# Sintetizador1.net
KiCad netlist of a schematic drawn in Altium Designer
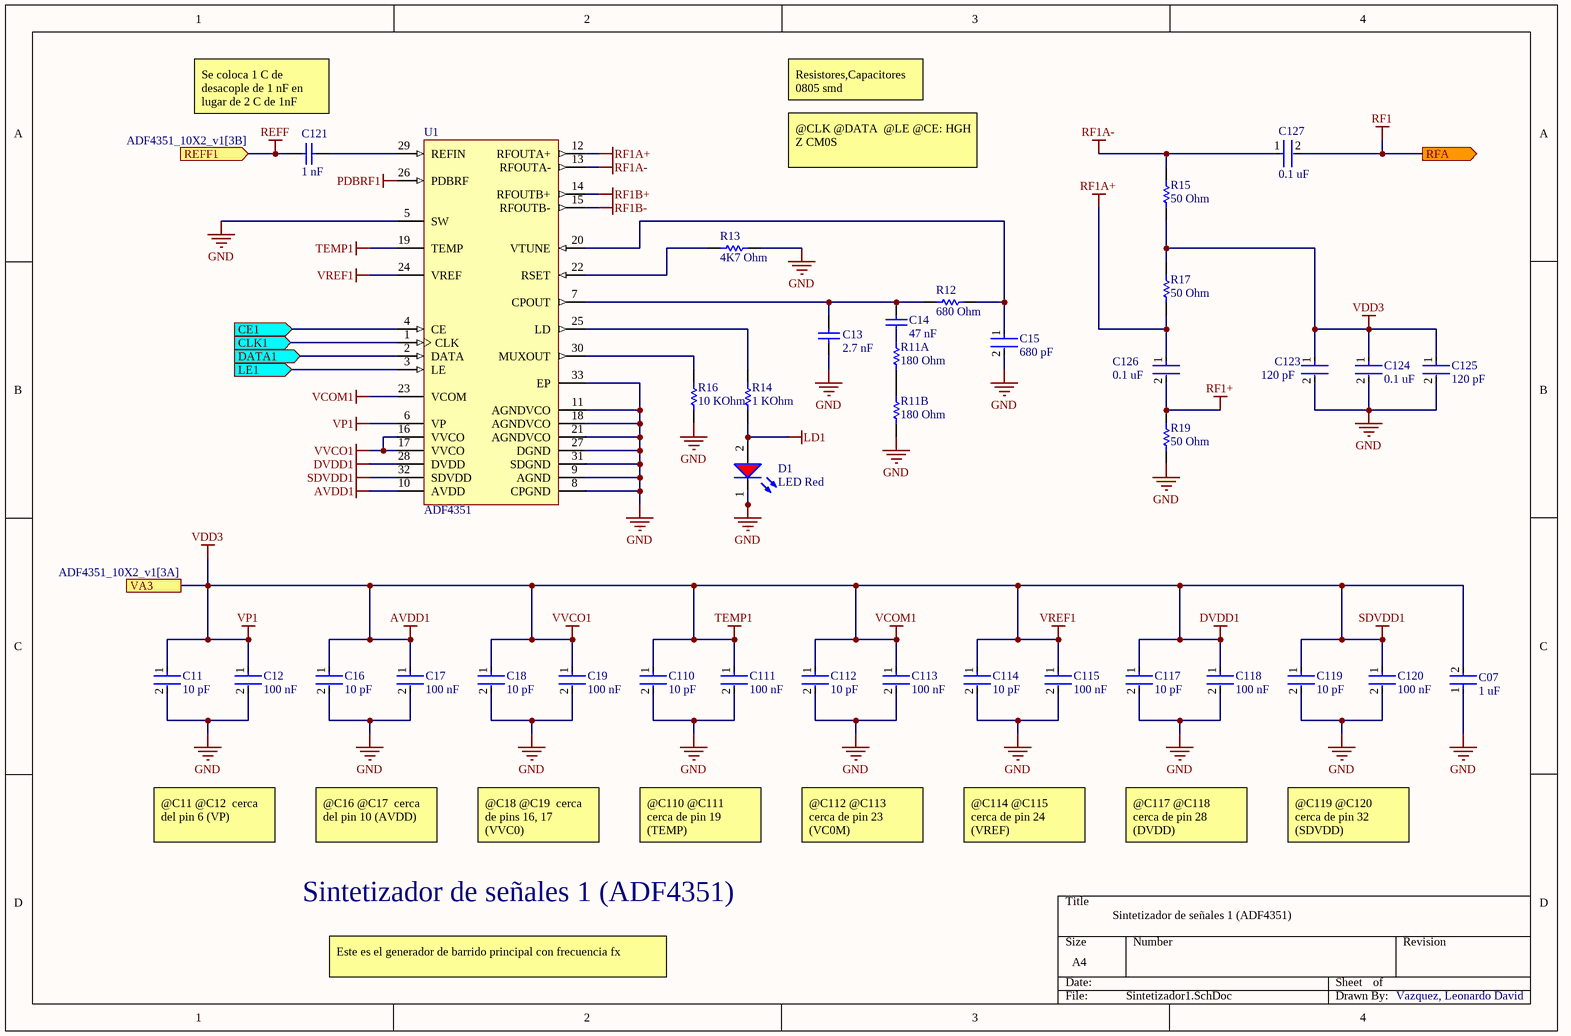
[diagram p0: Sintetizador1.SchDoc]

(export (version "E")
  (design (tool "Eeschema 10.0.6"))
  (components
    (comp (ref "C07")
      (value "1 uF")
      (footprint "FP-CC0805-0_85-MFG")
      (description "CAP CER 0.1UF 50V X7R 0805")
      (fields (field (name "TOLERANCE") "0.1") (field (name "MANUFACTURER PART NUMBER") "CC0805KRX7R9BB104"))
      (libsource (lib "Altium Content Vault") (part "11868f565c42a9108669ba33697ecf6"))
    )
    (comp (ref "C11")
      (value "10 pF")
      (footprint "FP-CL21-IPC_C")
      (description "CL21 Series 0805 10pF 100V ±0.25pF Tolerance C0G Multilayer Ceramic Chip Capacitor")
      (fields (field (name "VOLTAGE") "100V"))
      (libsource (lib "Altium Content Vault") (part "b4654b650e69147ec39a6b967a45e02"))
    )
    (comp (ref "C12")
      (value "100 nF")
      (footprint "FP-CL21-IPC_C")
      (description "CAP CER 0.1UF 50V X7R 0805")
      (fields (field (name "TOLERANCE") "0.1") (field (name "MANUFACTURER PART NUMBER") "CC0805KRX7R9BB104"))
      (libsource (lib "Altium Content Vault") (part "11868f565c42a9108669ba33697ecf6"))
    )
    (comp (ref "C13")
      (value "2.7 nF")
      (footprint "CAPC2013X130X50NL20T20")
      (fields (field (name "PART NUMBER") "CDR31BX272BKMSAJ") (field (name "MANUFACTURER") "Vitramon"))
      (libsource (lib "Altium Content Vault") (part "CAP"))
    )
    (comp (ref "C14")
      (value "47 nF")
      (footprint "CAPC2013X100X50ML20T25")
      (fields (field (name "MANUFACTURER") "Kemet") (field (name "PART NUMBER") "C0805F473K5RACTU"))
      (libsource (lib "Altium Content Vault") (part "CAP"))
    )
    (comp (ref "C15")
      (value "680 pF")
      (footprint "FP-C0805C-DN-MFG")
      (description "CAP CER 680PF 100V 5% NP0 0805")
      (fields
        (field (name "OCTOPART") "https://octopart.com/c0805c681j1gactu-kemet-8375796")
        (field (name "MANUFACTURER") "KEMET")
      )
      (libsource (lib "Altium Content Vault") (part "b4654b650e69147ec39a6b967a45e02"))
    )
    (comp (ref "C16")
      (value "10 pF")
      (footprint "FP-CL21-IPC_C")
      (description "CL21 Series 0805 10pF 100V ±0.25pF Tolerance C0G Multilayer Ceramic Chip Capacitor")
      (fields (field (name "VOLTAGE") "100V"))
      (libsource (lib "Altium Content Vault") (part "b4654b650e69147ec39a6b967a45e02"))
    )
    (comp (ref "C17")
      (value "100 nF")
      (footprint "FP-CL21-IPC_C")
      (description "CAP CER 0.1UF 50V X7R 0805")
      (fields (field (name "TOLERANCE") "0.1") (field (name "MANUFACTURER PART NUMBER") "CC0805KRX7R9BB104"))
      (libsource (lib "Altium Content Vault") (part "11868f565c42a9108669ba33697ecf6"))
    )
    (comp (ref "C18")
      (value "10 pF")
      (footprint "FP-CL21-IPC_C")
      (description "CL21 Series 0805 10pF 100V ±0.25pF Tolerance C0G Multilayer Ceramic Chip Capacitor")
      (fields (field (name "VOLTAGE") "100V"))
      (libsource (lib "Altium Content Vault") (part "b4654b650e69147ec39a6b967a45e02"))
    )
    (comp (ref "C19")
      (value "100 nF")
      (footprint "FP-CL21-IPC_C")
      (description "CAP CER 0.1UF 50V X7R 0805")
      (fields (field (name "TOLERANCE") "0.1") (field (name "MANUFACTURER PART NUMBER") "CC0805KRX7R9BB104"))
      (libsource (lib "Altium Content Vault") (part "11868f565c42a9108669ba33697ecf6"))
    )
    (comp (ref "C110")
      (value "10 pF")
      (footprint "FP-CL21-IPC_C")
      (description "CL21 Series 0805 10pF 100V ±0.25pF Tolerance C0G Multilayer Ceramic Chip Capacitor")
      (fields (field (name "VOLTAGE") "100V"))
      (libsource (lib "Altium Content Vault") (part "b4654b650e69147ec39a6b967a45e02"))
    )
    (comp (ref "C111")
      (value "100 nF")
      (footprint "FP-CL21-IPC_C")
      (description "CAP CER 0.1UF 50V X7R 0805")
      (fields (field (name "TOLERANCE") "0.1") (field (name "MANUFACTURER PART NUMBER") "CC0805KRX7R9BB104"))
      (libsource (lib "Altium Content Vault") (part "11868f565c42a9108669ba33697ecf6"))
    )
    (comp (ref "C112")
      (value "10 pF")
      (footprint "FP-CL21-IPC_C")
      (description "CL21 Series 0805 10pF 100V ±0.25pF Tolerance C0G Multilayer Ceramic Chip Capacitor")
      (fields (field (name "VOLTAGE") "100V"))
      (libsource (lib "Altium Content Vault") (part "b4654b650e69147ec39a6b967a45e02"))
    )
    (comp (ref "C113")
      (value "100 nF")
      (footprint "FP-CL21-IPC_C")
      (description "CAP CER 0.1UF 50V X7R 0805")
      (fields (field (name "TOLERANCE") "0.1") (field (name "MANUFACTURER PART NUMBER") "CC0805KRX7R9BB104"))
      (libsource (lib "Altium Content Vault") (part "11868f565c42a9108669ba33697ecf6"))
    )
    (comp (ref "C114")
      (value "10 pF")
      (footprint "FP-CL21-IPC_C")
      (description "CL21 Series 0805 10pF 100V ±0.25pF Tolerance C0G Multilayer Ceramic Chip Capacitor")
      (fields (field (name "VOLTAGE") "100V"))
      (libsource (lib "Altium Content Vault") (part "b4654b650e69147ec39a6b967a45e02"))
    )
    (comp (ref "C115")
      (value "100 nF")
      (footprint "FP-CL21-IPC_C")
      (description "CAP CER 0.1UF 50V X7R 0805")
      (fields (field (name "TOLERANCE") "0.1") (field (name "MANUFACTURER PART NUMBER") "CC0805KRX7R9BB104"))
      (libsource (lib "Altium Content Vault") (part "11868f565c42a9108669ba33697ecf6"))
    )
    (comp (ref "C117")
      (value "10 pF")
      (footprint "FP-CL21-IPC_C")
      (description "CL21 Series 0805 10pF 100V ±0.25pF Tolerance C0G Multilayer Ceramic Chip Capacitor")
      (fields (field (name "VOLTAGE") "100V"))
      (libsource (lib "Altium Content Vault") (part "b4654b650e69147ec39a6b967a45e02"))
    )
    (comp (ref "C118")
      (value "100 nF")
      (footprint "FP-CL21-IPC_C")
      (description "CAP CER 0.1UF 50V X7R 0805")
      (fields (field (name "TOLERANCE") "0.1") (field (name "MANUFACTURER PART NUMBER") "CC0805KRX7R9BB104"))
      (libsource (lib "Altium Content Vault") (part "11868f565c42a9108669ba33697ecf6"))
    )
    (comp (ref "C119")
      (value "10 pF")
      (footprint "FP-CL21-IPC_C")
      (description "CL21 Series 0805 10pF 100V ±0.25pF Tolerance C0G Multilayer Ceramic Chip Capacitor")
      (fields (field (name "VOLTAGE") "100V"))
      (libsource (lib "Altium Content Vault") (part "b4654b650e69147ec39a6b967a45e02"))
    )
    (comp (ref "C120")
      (value "100 nF")
      (footprint "FP-CL21-IPC_C")
      (description "CAP CER 0.1UF 50V X7R 0805")
      (fields (field (name "TOLERANCE") "0.1") (field (name "MANUFACTURER PART NUMBER") "CC0805KRX7R9BB104"))
      (libsource (lib "Altium Content Vault") (part "11868f565c42a9108669ba33697ecf6"))
    )
    (comp (ref "C121")
      (value "1 nF")
      (footprint "CAPC2013X94X50NL20T25")
      (fields
        (field (name "MANUFACTURER") "AVX Interconnect / Elco")
        (field (name "PART NUMBER") "08051A102J4T2A")
      )
      (libsource (lib "Altium Content Vault") (part "CAP"))
    )
    (comp (ref "C123")
      (value "120 pF")
      (footprint "FP-CC0805-0_85-MFG")
      (description "CAP CER 0.1UF 50V X7R 0805")
      (fields (field (name "TOLERANCE") "0.1") (field (name "MANUFACTURER PART NUMBER") "CC0805KRX7R9BB104"))
      (libsource (lib "Altium Content Vault") (part "11868f565c42a9108669ba33697ecf6"))
    )
    (comp (ref "C124")
      (value "0.1 uF")
      (footprint "FP-CC0805-0_85-MFG")
      (description "CAP CER 0.1UF 50V X7R 0805")
      (fields (field (name "TOLERANCE") "0.1") (field (name "MANUFACTURER PART NUMBER") "CC0805KRX7R9BB104"))
      (libsource (lib "Altium Content Vault") (part "11868f565c42a9108669ba33697ecf6"))
    )
    (comp (ref "C125")
      (value "120 pF")
      (footprint "FP-CC0805-0_85-MFG")
      (description "CAP CER 0.1UF 50V X7R 0805")
      (fields (field (name "TOLERANCE") "0.1") (field (name "MANUFACTURER PART NUMBER") "CC0805KRX7R9BB104"))
      (libsource (lib "Altium Content Vault") (part "11868f565c42a9108669ba33697ecf6"))
    )
    (comp (ref "C126")
      (value "0.1 uF")
      (footprint "FP-CC0805-0_85-MFG")
      (description "CAP CER 0.1UF 50V X7R 0805")
      (fields (field (name "TOLERANCE") "0.1") (field (name "MANUFACTURER PART NUMBER") "CC0805KRX7R9BB104"))
      (libsource (lib "Altium Content Vault") (part "11868f565c42a9108669ba33697ecf6"))
    )
    (comp (ref "C127")
      (value "0.1 uF")
      (footprint "FP-CC0805-0_85-MFG")
      (description "CAP CER 0.1UF 50V X7R 0805")
      (fields (field (name "TOLERANCE") "0.1") (field (name "MANUFACTURER PART NUMBER") "CC0805KRX7R9BB104"))
      (libsource (lib "Altium Content Vault") (part "11868f565c42a9108669ba33697ecf6"))
    )
    (comp (ref "D1")
      (value "LED Red")
      (footprint "WL-SMCW_0805_150080xx75000")
      (libsource (lib "Altium Content Vault") (part "LED_Red_2A-1K"))
    )
    (comp (ref "R11A")
      (value "180 Ohm")
      (footprint "RESC2013X70X40ML20T20")
      (fields (field (name "MANUFACTURER") "Panasonic") (field (name "PART NUMBER") "ERJ-6ENF3600V"))
      (libsource (lib "") (part "RES_2"))
    )
    (comp (ref "R11B")
      (value "180 Ohm")
      (footprint "RESC2013X70X40ML20T20")
      (fields (field (name "MANUFACTURER") "Panasonic") (field (name "PART NUMBER") "ERJ-6ENF3600V"))
      (libsource (lib "") (part "RES_1"))
    )
    (comp (ref "R12")
      (value "680 Ohm")
      (footprint "RESC2013X70X40ML20T20")
      (fields (field (name "PART NUMBER") "ERJ6ENF6803V") (field (name "MANUFACTURER") "Panasonic"))
      (libsource (lib "Altium Content Vault") (part "RES"))
    )
    (comp (ref "R13")
      (value "4K7 Ohm")
      (footprint "RESC2013X70X40ML20T20")
      (fields (field (name "PART NUMBER") "ERJ6ENF6803V") (field (name "MANUFACTURER") "Panasonic"))
      (libsource (lib "Altium Content Vault") (part "RES"))
    )
    (comp (ref "R14")
      (value "1 KOhm")
      (footprint "RESC2013X60X40ML20T25")
      (fields (field (name "MANUFACTURER") "Panasonic") (field (name "PART NUMBER") "ERA6AEB101V"))
      (libsource (lib "Altium Content Vault") (part "RES"))
    )
    (comp (ref "R15")
      (value "50 Ohm")
      (footprint "RESC2013X60X40ML20T25")
      (fields (field (name "MANUFACTURER") "Panasonic") (field (name "PART NUMBER") "ERA6AEB101V"))
      (libsource (lib "Altium Content Vault") (part "RES"))
    )
    (comp (ref "R16")
      (value "10 KOhm")
      (footprint "RESC2013X60X40ML20T25")
      (fields (field (name "MANUFACTURER") "Panasonic") (field (name "PART NUMBER") "ERA6AEB101V"))
      (libsource (lib "") (part "RES_3"))
    )
    (comp (ref "R17")
      (value "50 Ohm")
      (footprint "RESC2013X60X40ML20T25")
      (fields (field (name "MANUFACTURER") "Panasonic") (field (name "PART NUMBER") "ERA6AEB101V"))
      (libsource (lib "Altium Content Vault") (part "RES"))
    )
    (comp (ref "R19")
      (value "50 Ohm")
      (footprint "RESC2013X60X40ML20T25")
      (fields (field (name "MANUFACTURER") "Panasonic") (field (name "PART NUMBER") "ERA6AEB101V"))
      (libsource (lib "Altium Content Vault") (part "RES"))
    )
    (comp (ref "U1")
      (value "ADF4351")
      (footprint "ADI-CP-32-2_L")
      (description "Wideband Synthesizer with Integrated VCO, CP-32-2, Pb-Free, 1500 Reel")
      (libsource (lib "Altium Content Vault") (part "ADI-ADF4351-CP-32-2"))
    )
  )
  (nets
    (net (code "1") (name "/CE1") (class "Default")
      (node (ref "U1") (pin "4") (pinfunction "CE_4") (pintype "input"))
    )
    (net (code "2") (name "/CLK1") (class "Default")
      (node (ref "U1") (pin "1") (pinfunction "CLK_1") (pintype "input"))
    )
    (net (code "3") (name "/DATA1") (class "Default")
      (node (ref "U1") (pin "2") (pinfunction "DATA_2") (pintype "input"))
    )
    (net (code "4") (name "/LE1") (class "Default")
      (node (ref "U1") (pin "3") (pinfunction "LE_3") (pintype "input"))
    )
    (net (code "5") (name "AVDD1") (class "Default")
      (node (ref "C07") (pin "2") (pinfunction "2_2") (pintype "passive"))
      (node (ref "C11") (pin "1") (pinfunction "1_1") (pintype "passive"))
      (node (ref "C110") (pin "1") (pinfunction "1_1") (pintype "passive"))
      (node (ref "C111") (pin "1") (pinfunction "1_1") (pintype "passive"))
      (node (ref "C112") (pin "1") (pinfunction "1_1") (pintype "passive"))
      (node (ref "C113") (pin "1") (pinfunction "1_1") (pintype "passive"))
      (node (ref "C114") (pin "1") (pinfunction "1_1") (pintype "passive"))
      (node (ref "C115") (pin "1") (pinfunction "1_1") (pintype "passive"))
      (node (ref "C117") (pin "1") (pinfunction "1_1") (pintype "passive"))
      (node (ref "C118") (pin "1") (pinfunction "1_1") (pintype "passive"))
      (node (ref "C119") (pin "1") (pinfunction "1_1") (pintype "passive"))
      (node (ref "C12") (pin "1") (pinfunction "1_1") (pintype "passive"))
      (node (ref "C120") (pin "1") (pinfunction "1_1") (pintype "passive"))
      (node (ref "C123") (pin "1") (pinfunction "1_1") (pintype "passive"))
      (node (ref "C124") (pin "1") (pinfunction "1_1") (pintype "passive"))
      (node (ref "C125") (pin "1") (pinfunction "1_1") (pintype "passive"))
      (node (ref "C16") (pin "1") (pinfunction "1_1") (pintype "passive"))
      (node (ref "C17") (pin "1") (pinfunction "1_1") (pintype "passive"))
      (node (ref "C18") (pin "1") (pinfunction "1_1") (pintype "passive"))
      (node (ref "C19") (pin "1") (pinfunction "1_1") (pintype "passive"))
      (node (ref "R15") (pin "2") (pinfunction "2_2") (pintype "passive"))
      (node (ref "R17") (pin "1") (pinfunction "1_1") (pintype "passive"))
      (node (ref "U1") (pin "10") (pinfunction "AVDD_10") (pintype "power_in"))
      (node (ref "U1") (pin "16") (pinfunction "VVCO_16") (pintype "power_in"))
      (node (ref "U1") (pin "17") (pinfunction "VVCO_17") (pintype "power_in"))
      (node (ref "U1") (pin "19") (pinfunction "TEMP_19") (pintype "passive"))
      (node (ref "U1") (pin "23") (pinfunction "VCOM_23") (pintype "passive"))
      (node (ref "U1") (pin "24") (pinfunction "VREF_24") (pintype "passive"))
      (node (ref "U1") (pin "28") (pinfunction "DVDD_28") (pintype "power_in"))
      (node (ref "U1") (pin "32") (pinfunction "SDVDD_32") (pintype "power_in"))
      (node (ref "U1") (pin "6") (pinfunction "VP_6") (pintype "power_in"))
    )
    (net (code "6") (name "GND") (class "Default")
      (node (ref "C07") (pin "1") (pinfunction "1_1") (pintype "passive"))
      (node (ref "C11") (pin "2") (pinfunction "2_2") (pintype "passive"))
      (node (ref "C110") (pin "2") (pinfunction "2_2") (pintype "passive"))
      (node (ref "C111") (pin "2") (pinfunction "2_2") (pintype "passive"))
      (node (ref "C112") (pin "2") (pinfunction "2_2") (pintype "passive"))
      (node (ref "C113") (pin "2") (pinfunction "2_2") (pintype "passive"))
      (node (ref "C114") (pin "2") (pinfunction "2_2") (pintype "passive"))
      (node (ref "C115") (pin "2") (pinfunction "2_2") (pintype "passive"))
      (node (ref "C117") (pin "2") (pinfunction "2_2") (pintype "passive"))
      (node (ref "C118") (pin "2") (pinfunction "2_2") (pintype "passive"))
      (node (ref "C119") (pin "2") (pinfunction "2_2") (pintype "passive"))
      (node (ref "C12") (pin "2") (pinfunction "2_2") (pintype "passive"))
      (node (ref "C120") (pin "2") (pinfunction "2_2") (pintype "passive"))
      (node (ref "C123") (pin "2") (pinfunction "2_2") (pintype "passive"))
      (node (ref "C124") (pin "2") (pinfunction "2_2") (pintype "passive"))
      (node (ref "C125") (pin "2") (pinfunction "2_2") (pintype "passive"))
      (node (ref "C13") (pin "1") (pinfunction "1_1") (pintype "passive"))
      (node (ref "C15") (pin "2") (pinfunction "2_2") (pintype "passive"))
      (node (ref "C16") (pin "2") (pinfunction "2_2") (pintype "passive"))
      (node (ref "C17") (pin "2") (pinfunction "2_2") (pintype "passive"))
      (node (ref "C18") (pin "2") (pinfunction "2_2") (pintype "passive"))
      (node (ref "C19") (pin "2") (pinfunction "2_2") (pintype "passive"))
      (node (ref "D1") (pin "1") (pinfunction "K_1") (pintype "passive"))
      (node (ref "R11B") (pin "1") (pinfunction "1_1") (pintype "passive"))
      (node (ref "R13") (pin "2") (pinfunction "2_2") (pintype "passive"))
      (node (ref "R16") (pin "2") (pinfunction "2_2") (pintype "passive"))
      (node (ref "R19") (pin "2") (pinfunction "2_2") (pintype "passive"))
      (node (ref "U1") (pin "11") (pinfunction "AGNDVCO_11") (pintype "power_in"))
      (node (ref "U1") (pin "18") (pinfunction "AGNDVCO_18") (pintype "power_in"))
      (node (ref "U1") (pin "21") (pinfunction "AGNDVCO_21") (pintype "power_in"))
      (node (ref "U1") (pin "27") (pinfunction "DGND_27") (pintype "power_in"))
      (node (ref "U1") (pin "31") (pinfunction "SDGND_31") (pintype "power_in"))
      (node (ref "U1") (pin "33") (pinfunction "EP_33") (pintype "power_in"))
      (node (ref "U1") (pin "5") (pinfunction "SW_5") (pintype "passive"))
      (node (ref "U1") (pin "8") (pinfunction "CPGND_8") (pintype "power_in"))
      (node (ref "U1") (pin "9") (pinfunction "AGND_9") (pintype "power_in"))
    )
    (net (code "7") (name "LD1") (class "Default")
      (node (ref "D1") (pin "2") (pinfunction "A_2") (pintype "passive"))
      (node (ref "R14") (pin "1") (pinfunction "1_1") (pintype "passive"))
    )
    (net (code "8") (name "Net-(C14-Pad1)") (class "Default")
      (node (ref "C14") (pin "1") (pinfunction "1_1") (pintype "passive"))
      (node (ref "R11A") (pin "2") (pinfunction "2_2") (pintype "passive"))
    )
    (net (code "9") (name "Net-(R11A-Pad2)") (class "Default")
      (node (ref "R11A") (pin "2") (pinfunction "2_2") (pintype "passive"))
      (node (ref "R11B") (pin "1") (pinfunction "1_1") (pintype "passive"))
    )
    (net (code "10") (name "Net-(U1-CPOUT)") (class "Default")
      (node (ref "C13") (pin "2") (pinfunction "2_2") (pintype "passive"))
      (node (ref "C14") (pin "2") (pinfunction "2_2") (pintype "passive"))
      (node (ref "R12") (pin "1") (pinfunction "1_1") (pintype "passive"))
      (node (ref "U1") (pin "7") (pinfunction "CPOUT_7") (pintype "output"))
    )
    (net (code "11") (name "Net-(U1-LD)") (class "Default")
      (node (ref "R14") (pin "2") (pinfunction "2_2") (pintype "passive"))
      (node (ref "U1") (pin "25") (pinfunction "LD_25") (pintype "output"))
    )
    (net (code "12") (name "Net-(U1-MUXOUT)") (class "Default")
      (node (ref "R16") (pin "1") (pinfunction "1_1") (pintype "passive"))
      (node (ref "U1") (pin "30") (pinfunction "MUXOUT_30") (pintype "output"))
    )
    (net (code "13") (name "Net-(U1-REFIN)") (class "Default")
      (node (ref "C121") (pin "2") (pinfunction "2_2") (pintype "passive"))
      (node (ref "U1") (pin "29") (pinfunction "REFIN_29") (pintype "input"))
    )
    (net (code "14") (name "Net-(U1-RSET)") (class "Default")
      (node (ref "R13") (pin "1") (pinfunction "1_1") (pintype "passive"))
      (node (ref "U1") (pin "22") (pinfunction "RSET_22") (pintype "input"))
    )
    (net (code "15") (name "Net-(U1-VTUNE)") (class "Default")
      (node (ref "C15") (pin "1") (pinfunction "1_1") (pintype "passive"))
      (node (ref "R12") (pin "2") (pinfunction "2_2") (pintype "passive"))
      (node (ref "U1") (pin "20") (pinfunction "VTUNE_20") (pintype "input"))
    )
    (net (code "16") (name "PDBRF1") (class "Default")
      (node (ref "U1") (pin "26") (pinfunction "PDBRF_26") (pintype "input"))
    )
    (net (code "17") (name "REFF") (class "Default")
      (node (ref "C121") (pin "1") (pinfunction "1_1") (pintype "passive"))
    )
    (net (code "18") (name "RF1") (class "Default")
      (node (ref "C127") (pin "2") (pinfunction "2_2") (pintype "passive"))
    )
    (net (code "19") (name "RF1+") (class "Default")
      (node (ref "C126") (pin "2") (pinfunction "2_2") (pintype "passive"))
      (node (ref "R19") (pin "1") (pinfunction "1_1") (pintype "passive"))
    )
    (net (code "20") (name "RF1A+") (class "Default")
      (node (ref "C126") (pin "1") (pinfunction "1_1") (pintype "passive"))
      (node (ref "R17") (pin "2") (pinfunction "2_2") (pintype "passive"))
      (node (ref "U1") (pin "12") (pinfunction "RFOUTA+_12") (pintype "output"))
    )
    (net (code "21") (name "RF1A-") (class "Default")
      (node (ref "C127") (pin "1") (pinfunction "1_1") (pintype "passive"))
      (node (ref "R15") (pin "1") (pinfunction "1_1") (pintype "passive"))
      (node (ref "U1") (pin "13") (pinfunction "RFOUTA-_13") (pintype "output"))
    )
    (net (code "22") (name "RF1B+") (class "Default")
      (node (ref "U1") (pin "14") (pinfunction "RFOUTB+_14") (pintype "output"))
    )
    (net (code "23") (name "RF1B-") (class "Default")
      (node (ref "U1") (pin "15") (pinfunction "RFOUTB-_15") (pintype "output"))
    )
  )
)
